# Power.net
KiCad netlist of a schematic drawn in Altium Designer
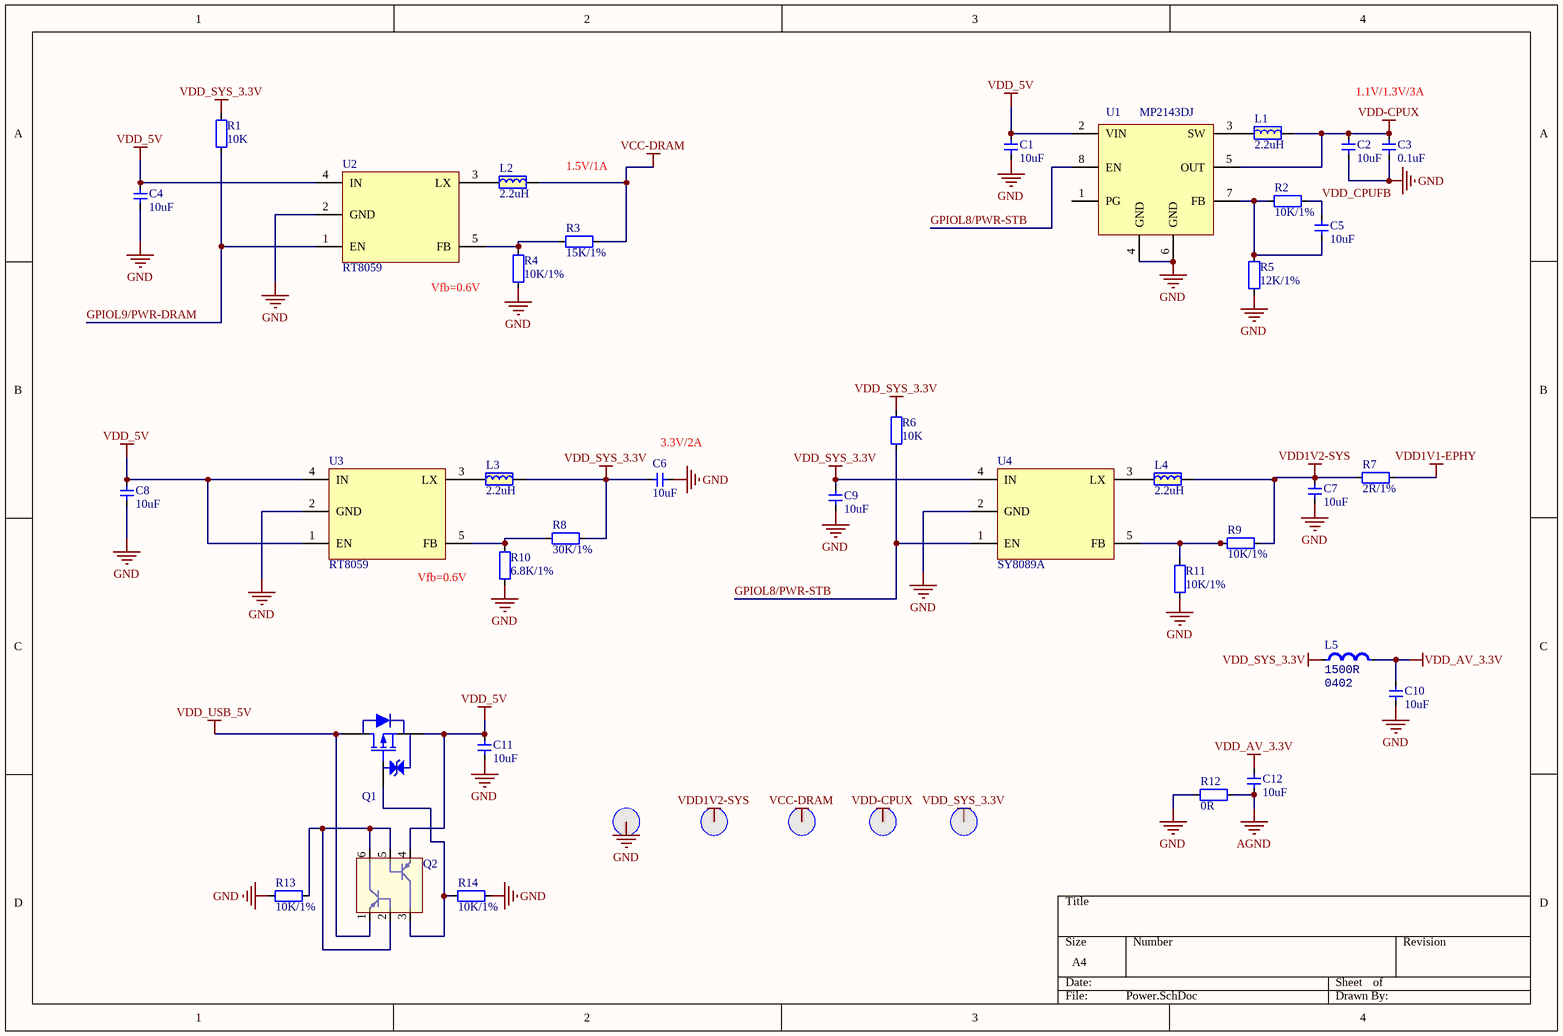
[diagram p0: Power.SchDoc]

(export (version "E")
  (design (tool "Eeschema 10.0.6"))
  (components
    (comp (ref "C1")
      (value "10uF")
      (footprint "CAP_0402")
      (description "Capacitor")
      (libsource (lib "MyPcbLib") (part "电容-0402"))
    )
    (comp (ref "C2")
      (value "10uF")
      (footprint "CAP_0402")
      (description "Capacitor")
      (libsource (lib "MyPcbLib") (part "电容-0402"))
    )
    (comp (ref "C3")
      (value "0.1uF")
      (footprint "CAP_0402")
      (description "Capacitor")
      (libsource (lib "MyPcbLib") (part "电容-0402"))
    )
    (comp (ref "C4")
      (value "10uF")
      (footprint "CAP_0402")
      (description "Capacitor")
      (libsource (lib "MyPcbLib") (part "电容-0402"))
    )
    (comp (ref "C5")
      (value "10uF")
      (footprint "CAP_0402")
      (description "Capacitor")
      (libsource (lib "MyPcbLib") (part "电容-0402"))
    )
    (comp (ref "C6")
      (value "10uF")
      (footprint "CAP_0402")
      (description "Capacitor")
      (libsource (lib "MyPcbLib") (part "电容-0402"))
    )
    (comp (ref "C7")
      (value "10uF")
      (footprint "CAP_0402")
      (description "Capacitor")
      (libsource (lib "MyPcbLib") (part "电容-0402"))
    )
    (comp (ref "C8")
      (value "10uF")
      (footprint "CAP_0402")
      (description "Capacitor")
      (libsource (lib "MyPcbLib") (part "电容-0402"))
    )
    (comp (ref "C9")
      (value "10uF")
      (footprint "CAP_0402")
      (description "Capacitor")
      (libsource (lib "MyPcbLib") (part "电容-0402"))
    )
    (comp (ref "C10")
      (value "10uF")
      (footprint "CAP_0402")
      (description "Capacitor")
      (libsource (lib "MyPcbLib") (part "电容-0402"))
    )
    (comp (ref "C11")
      (value "10uF")
      (footprint "CAP_0402")
      (description "Capacitor")
      (libsource (lib "MyPcbLib") (part "电容-0402"))
    )
    (comp (ref "C12")
      (value "10uF")
      (footprint "CAP_0402")
      (description "Capacitor")
      (libsource (lib "MyPcbLib") (part "电容-0402"))
    )
    (comp (ref "L1")
      (value "2.2uH")
      (footprint "2520-L")
      (description "磁珠")
      (libsource (lib "MyPcbLib") (part "电感-2520"))
    )
    (comp (ref "L2")
      (value "2.2uH")
      (footprint "2520-L")
      (description "磁珠")
      (libsource (lib "MyPcbLib") (part "电感-2520"))
    )
    (comp (ref "L3")
      (value "2.2uH")
      (footprint "2520-L")
      (description "磁珠")
      (libsource (lib "MyPcbLib") (part "电感-2520"))
    )
    (comp (ref "L4")
      (value "2.2uH")
      (footprint "2520-L")
      (description "磁珠")
      (libsource (lib "MyPcbLib") (part "电感-2520"))
    )
    (comp (ref "L5")
      (value "1500R")
      (footprint "IND_0402")
      (description "Inductor")
      (fields (field (name "TYPE") "0402") (field (name "Comment") "H0402"))
      (libsource (lib "KitSprout") (part "Ind_0402"))
    )
    (comp (ref "Q1")
      (value "AO3415A")
      (footprint "SOT23-3")
      (description "MOSFET")
      (fields (field (name "PUBLISHER") "Altium Limited"))
      (libsource (lib "MyPcbLib") (part "AO3415A"))
    )
    (comp (ref "Q2")
      (value "BCM856BS")
      (footprint "SOT363-6")
      (description "Transistor")
      (libsource (lib "MyPcbLib") (part "BCM856BS"))
    )
    (comp (ref "R1")
      (value "10K")
      (footprint "RES_0402")
      (description "Resistor")
      (libsource (lib "") (part "电阻-0402_1"))
    )
    (comp (ref "R2")
      (value "10K/1%")
      (footprint "RES_0402")
      (description "Resistor")
      (libsource (lib "MyPcbLib") (part "电阻-0402"))
    )
    (comp (ref "R3")
      (value "15K/1%")
      (footprint "RES_0402")
      (description "Resistor")
      (libsource (lib "") (part "电阻-0402_2"))
    )
    (comp (ref "R4")
      (value "10K/1%")
      (footprint "RES_0402")
      (description "Resistor")
      (libsource (lib "") (part "电阻-0402_1"))
    )
    (comp (ref "R5")
      (value "12K/1%")
      (footprint "RES_0402")
      (description "Resistor")
      (libsource (lib "") (part "电阻-0402_1"))
    )
    (comp (ref "R6")
      (value "10K")
      (footprint "RES_0402")
      (description "Resistor")
      (libsource (lib "") (part "电阻-0402_1"))
    )
    (comp (ref "R7")
      (value "2R/1%")
      (footprint "RES_0402")
      (description "Resistor")
      (libsource (lib "MyPcbLib") (part "电阻-0402"))
    )
    (comp (ref "R8")
      (value "30K/1%")
      (footprint "RES_0402")
      (description "Resistor")
      (libsource (lib "") (part "电阻-0402_2"))
    )
    (comp (ref "R9")
      (value "10K/1%")
      (footprint "RES_0402")
      (description "Resistor")
      (libsource (lib "MyPcbLib") (part "电阻-0402"))
    )
    (comp (ref "R10")
      (value "6.8K/1%")
      (footprint "RES_0402")
      (description "Resistor")
      (libsource (lib "") (part "电阻-0402_1"))
    )
    (comp (ref "R11")
      (value "10K/1%")
      (footprint "RES_0402")
      (description "Resistor")
      (libsource (lib "") (part "电阻-0402_1"))
    )
    (comp (ref "R12")
      (value "0R")
      (footprint "RES_0402")
      (description "Resistor")
      (libsource (lib "") (part "电阻-0402_2"))
    )
    (comp (ref "R13")
      (value "10K/1%")
      (footprint "RES_0402")
      (description "Resistor")
      (libsource (lib "MyPcbLib") (part "电阻-0402"))
    )
    (comp (ref "R14")
      (value "10K/1%")
      (footprint "RES_0402")
      (description "Resistor")
      (libsource (lib "MyPcbLib") (part "电阻-0402"))
    )
    (comp (ref "T1") (value "测试点") (footprint "TEST_PT") (libsource (lib "MyPcbLib") (part "测试点")))
    (comp (ref "T2") (value "测试点") (footprint "TEST_PT") (libsource (lib "MyPcbLib") (part "测试点")))
    (comp (ref "T3") (value "测试点") (footprint "TEST_PT") (libsource (lib "MyPcbLib") (part "测试点")))
    (comp (ref "T4") (value "测试点") (footprint "TEST_PT") (libsource (lib "MyPcbLib") (part "测试点")))
    (comp (ref "T5") (value "测试点") (footprint "TEST_PT") (libsource (lib "MyPcbLib") (part "测试点")))
    (comp (ref "U1")
      (value "MP2143DJ")
      (footprint "SOT23-8")
      (description "LDO")
      (libsource (lib "MyPcbLib") (part "MP2143DJ"))
    )
    (comp (ref "U2")
      (value "RT8059")
      (footprint "SOT23-5")
      (description "LDO")
      (libsource (lib "MyPcbLib") (part "RT8059"))
    )
    (comp (ref "U3")
      (value "RT8059")
      (footprint "SOT23-5")
      (description "LDO")
      (libsource (lib "MyPcbLib") (part "RT8059"))
    )
    (comp (ref "U4")
      (value "SY8089A")
      (footprint "SOT23-5")
      (description "LDO")
      (libsource (lib "MyPcbLib") (part "SY8089A"))
    )
  )
  (nets
    (net (code "1") (name "/GPIOL8{slash}PWR-STB") (class "Default")
      (node (ref "R6") (pin "1") (pinfunction "1_1") (pintype "passive"))
      (node (ref "U1") (pin "8") (pinfunction "EN_8") (pintype "passive"))
      (node (ref "U4") (pin "1") (pinfunction "EN_1") (pintype "passive"))
    )
    (net (code "2") (name "/GPIOL9{slash}PWR-DRAM") (class "Default")
      (node (ref "R1") (pin "1") (pinfunction "1_1") (pintype "passive"))
      (node (ref "U2") (pin "1") (pinfunction "EN_1") (pintype "passive"))
    )
    (net (code "3") (name "/VDD_CPUFB") (class "Default")
      (node (ref "C5") (pin "2") (pinfunction "2_2") (pintype "passive"))
      (node (ref "R2") (pin "2") (pinfunction "2_2") (pintype "passive"))
    )
    (net (code "4") (name "AGND") (class "Default")
      (node (ref "C12") (pin "1") (pinfunction "1_1") (pintype "passive"))
      (node (ref "R12") (pin "1") (pinfunction "1_1") (pintype "passive"))
    )
    (net (code "5") (name "GND") (class "Default")
      (node (ref "C1") (pin "1") (pinfunction "1_1") (pintype "passive"))
      (node (ref "C10") (pin "1") (pinfunction "1_1") (pintype "passive"))
      (node (ref "C11") (pin "1") (pinfunction "1_1") (pintype "passive"))
      (node (ref "C2") (pin "1") (pinfunction "1_1") (pintype "passive"))
      (node (ref "C3") (pin "1") (pinfunction "1_1") (pintype "passive"))
      (node (ref "C4") (pin "1") (pinfunction "1_1") (pintype "passive"))
      (node (ref "C6") (pin "1") (pinfunction "1_1") (pintype "passive"))
      (node (ref "C7") (pin "1") (pinfunction "1_1") (pintype "passive"))
      (node (ref "C8") (pin "1") (pinfunction "1_1") (pintype "passive"))
      (node (ref "C9") (pin "1") (pinfunction "1_1") (pintype "passive"))
      (node (ref "R10") (pin "1") (pinfunction "1_1") (pintype "passive"))
      (node (ref "R11") (pin "1") (pinfunction "1_1") (pintype "passive"))
      (node (ref "R12") (pin "2") (pinfunction "2_2") (pintype "passive"))
      (node (ref "R13") (pin "1") (pinfunction "1_1") (pintype "passive"))
      (node (ref "R14") (pin "2") (pinfunction "2_2") (pintype "passive"))
      (node (ref "R4") (pin "1") (pinfunction "1_1") (pintype "passive"))
      (node (ref "R5") (pin "1") (pinfunction "1_1") (pintype "passive"))
      (node (ref "T1") (pin "0") (pinfunction "0_0") (pintype "passive"))
      (node (ref "U1") (pin "4") (pinfunction "GND_4") (pintype "passive"))
      (node (ref "U1") (pin "6") (pinfunction "GND_6") (pintype "passive"))
      (node (ref "U2") (pin "2") (pinfunction "GND_2") (pintype "passive"))
      (node (ref "U3") (pin "2") (pinfunction "GND_2") (pintype "passive"))
      (node (ref "U4") (pin "2") (pinfunction "GND_2") (pintype "passive"))
    )
    (net (code "6") (name "Net-(Q1-G)") (class "Default")
      (node (ref "Q1") (pin "1") (pinfunction "G_1") (pintype "passive"))
      (node (ref "Q2") (pin "3") (pintype "passive"))
      (node (ref "R14") (pin "1") (pinfunction "1_1") (pintype "passive"))
    )
    (net (code "7") (name "Net-(Q2-Pad2)") (class "Default")
      (node (ref "Q2") (pin "2") (pintype "passive"))
      (node (ref "Q2") (pin "5") (pintype "passive"))
      (node (ref "Q2") (pin "6") (pintype "passive"))
      (node (ref "R13") (pin "2") (pinfunction "2_2") (pintype "passive"))
    )
    (net (code "8") (name "Net-(U1-FB)") (class "Default")
      (node (ref "C5") (pin "1") (pinfunction "1_1") (pintype "passive"))
      (node (ref "R2") (pin "1") (pinfunction "1_1") (pintype "passive"))
      (node (ref "R5") (pin "2") (pinfunction "2_2") (pintype "passive"))
      (node (ref "U1") (pin "7") (pinfunction "FB_7") (pintype "passive"))
    )
    (net (code "9") (name "Net-(U1-SW)") (class "Default")
      (node (ref "L1") (pin "1") (pintype "passive"))
      (node (ref "U1") (pin "3") (pinfunction "SW_3") (pintype "passive"))
    )
    (net (code "10") (name "Net-(U2-FB)") (class "Default")
      (node (ref "R3") (pin "2") (pinfunction "2_2") (pintype "passive"))
      (node (ref "R4") (pin "2") (pinfunction "2_2") (pintype "passive"))
      (node (ref "U2") (pin "5") (pinfunction "FB_5") (pintype "passive"))
    )
    (net (code "11") (name "Net-(U2-LX)") (class "Default")
      (node (ref "L2") (pin "1") (pintype "passive"))
      (node (ref "U2") (pin "3") (pinfunction "LX_3") (pintype "passive"))
    )
    (net (code "12") (name "Net-(U3-FB)") (class "Default")
      (node (ref "R10") (pin "2") (pinfunction "2_2") (pintype "passive"))
      (node (ref "R8") (pin "2") (pinfunction "2_2") (pintype "passive"))
      (node (ref "U3") (pin "5") (pinfunction "FB_5") (pintype "passive"))
    )
    (net (code "13") (name "Net-(U3-LX)") (class "Default")
      (node (ref "L3") (pin "1") (pintype "passive"))
      (node (ref "U3") (pin "3") (pinfunction "LX_3") (pintype "passive"))
    )
    (net (code "14") (name "Net-(U4-FB)") (class "Default")
      (node (ref "R11") (pin "2") (pinfunction "2_2") (pintype "passive"))
      (node (ref "R9") (pin "1") (pinfunction "1_1") (pintype "passive"))
      (node (ref "U4") (pin "5") (pinfunction "FB_5") (pintype "passive"))
    )
    (net (code "15") (name "Net-(U4-LX)") (class "Default")
      (node (ref "L4") (pin "1") (pintype "passive"))
      (node (ref "U4") (pin "3") (pinfunction "LX_3") (pintype "passive"))
    )
    (net (code "16") (name "VCC-DRAM") (class "Default")
      (node (ref "L2") (pin "2") (pinfunction "2_2") (pintype "passive"))
      (node (ref "R3") (pin "1") (pinfunction "1_1") (pintype "passive"))
      (node (ref "T3") (pin "0") (pinfunction "0_0") (pintype "passive"))
    )
    (net (code "17") (name "VDD-CPUX") (class "Default")
      (node (ref "C2") (pin "2") (pinfunction "2_2") (pintype "passive"))
      (node (ref "C3") (pin "2") (pinfunction "2_2") (pintype "passive"))
      (node (ref "L1") (pin "2") (pinfunction "2_2") (pintype "passive"))
      (node (ref "T4") (pin "0") (pinfunction "0_0") (pintype "passive"))
      (node (ref "U1") (pin "5") (pinfunction "OUT_5") (pintype "passive"))
    )
    (net (code "18") (name "VDD1V1-EPHY") (class "Default")
      (node (ref "R7") (pin "2") (pinfunction "2_2") (pintype "passive"))
    )
    (net (code "19") (name "VDD1V2-SYS") (class "Default")
      (node (ref "C7") (pin "2") (pinfunction "2_2") (pintype "passive"))
      (node (ref "L4") (pin "2") (pinfunction "2_2") (pintype "passive"))
      (node (ref "R7") (pin "1") (pinfunction "1_1") (pintype "passive"))
      (node (ref "R9") (pin "2") (pinfunction "2_2") (pintype "passive"))
      (node (ref "T2") (pin "0") (pinfunction "0_0") (pintype "passive"))
    )
    (net (code "20") (name "VDD_5V") (class "Default")
      (node (ref "C1") (pin "2") (pinfunction "2_2") (pintype "passive"))
      (node (ref "C11") (pin "2") (pinfunction "2_2") (pintype "passive"))
      (node (ref "C4") (pin "2") (pinfunction "2_2") (pintype "passive"))
      (node (ref "C8") (pin "2") (pinfunction "2_2") (pintype "passive"))
      (node (ref "Q1") (pin "2") (pinfunction "S_2") (pintype "passive"))
      (node (ref "Q2") (pin "4") (pintype "passive"))
      (node (ref "U1") (pin "2") (pinfunction "VIN_2") (pintype "passive"))
      (node (ref "U2") (pin "4") (pinfunction "IN_4") (pintype "passive"))
      (node (ref "U3") (pin "1") (pinfunction "EN_1") (pintype "passive"))
      (node (ref "U3") (pin "4") (pinfunction "IN_4") (pintype "passive"))
    )
    (net (code "21") (name "VDD_AV_3.3V") (class "Default")
      (node (ref "C10") (pin "2") (pinfunction "2_2") (pintype "passive"))
      (node (ref "C12") (pin "2") (pinfunction "2_2") (pintype "passive"))
      (node (ref "L5") (pin "2") (pinfunction "2_2") (pintype "passive"))
    )
    (net (code "22") (name "VDD_SYS_3.3V") (class "Default")
      (node (ref "C6") (pin "2") (pinfunction "2_2") (pintype "passive"))
      (node (ref "C9") (pin "2") (pinfunction "2_2") (pintype "passive"))
      (node (ref "L3") (pin "2") (pinfunction "2_2") (pintype "passive"))
      (node (ref "L5") (pin "1") (pinfunction "1_1") (pintype "passive"))
      (node (ref "R1") (pin "2") (pinfunction "2_2") (pintype "passive"))
      (node (ref "R6") (pin "2") (pinfunction "2_2") (pintype "passive"))
      (node (ref "R8") (pin "1") (pinfunction "1_1") (pintype "passive"))
      (node (ref "T5") (pin "0") (pinfunction "0_0") (pintype "passive"))
      (node (ref "U4") (pin "4") (pinfunction "IN_4") (pintype "passive"))
    )
    (net (code "23") (name "VDD_USB_5V") (class "Default")
      (node (ref "Q1") (pin "3") (pinfunction "D_3") (pintype "passive"))
      (node (ref "Q2") (pin "1") (pintype "passive"))
    )
    (net (code "24") (name "unconnected-(U1-PG-Pad1)") (class "Default")
      (node (ref "U1") (pin "1") (pinfunction "PG_1") (pintype "passive"))
    )
  )
)
